# Power.net
KiCad netlist of a schematic drawn in Altium Designer
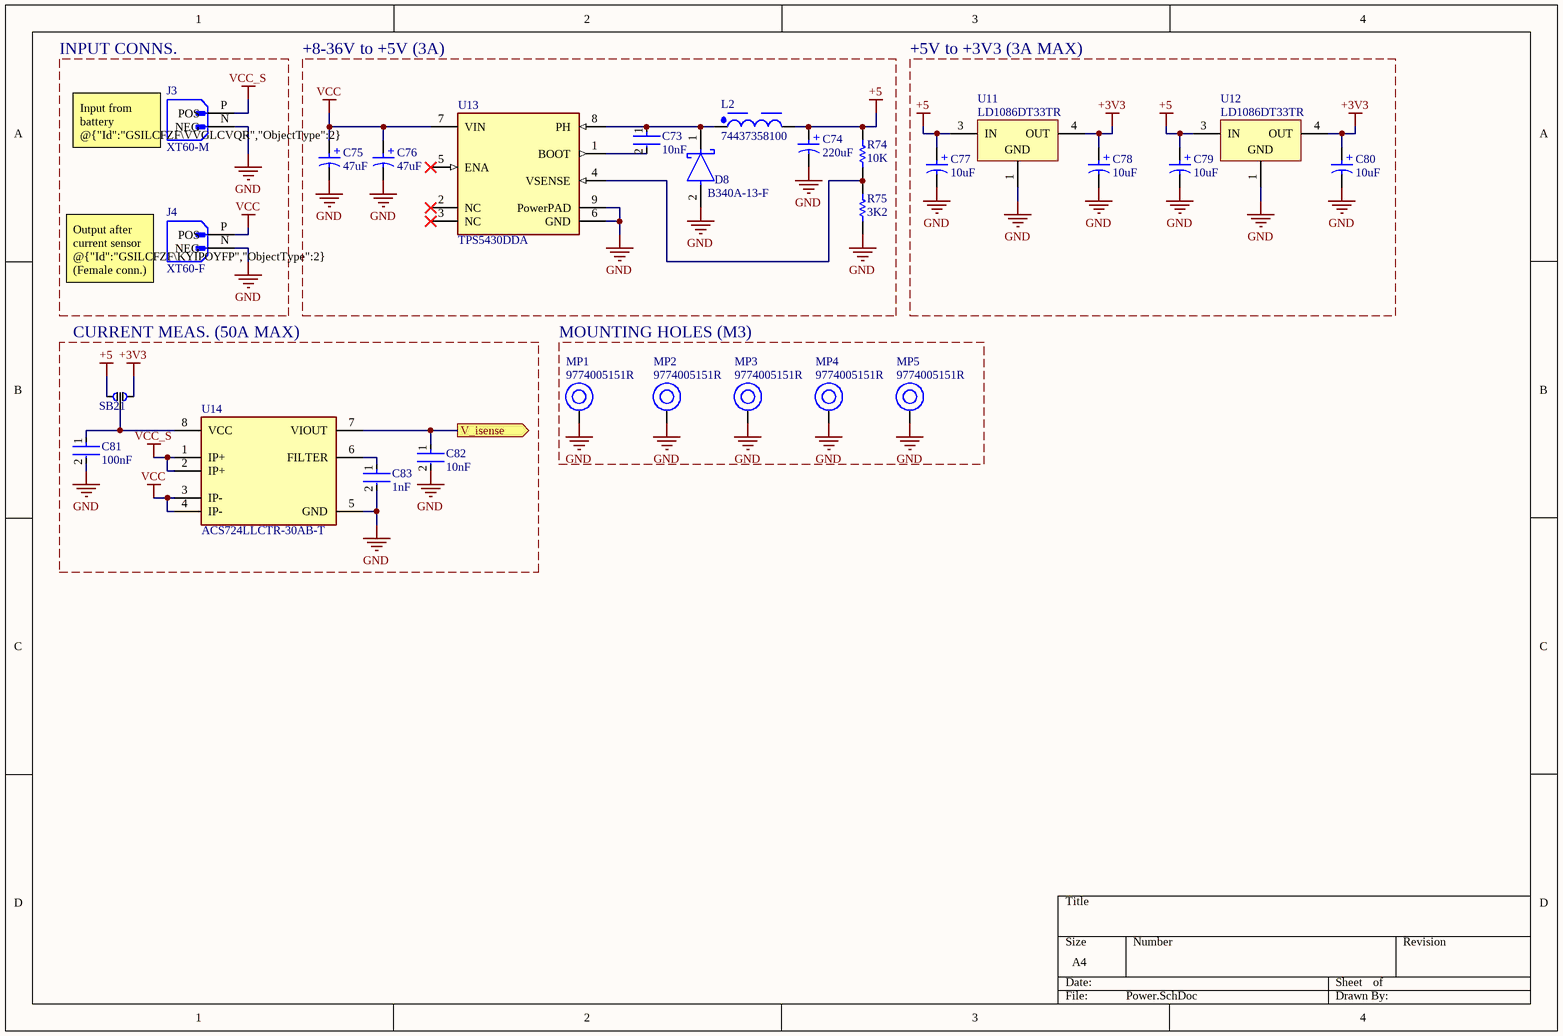
[diagram p0: Power.SchDoc]

(export (version "E")
  (design (tool "Eeschema 10.0.6"))
  (components
    (comp (ref "C73")
      (value "10nF")
      (footprint "FP-GRM188-0_1-e0_2_0_55-IPC_A")
      (description "Chip Multilayer Ceramic Capacitors for General Purpose, 0603, 10uF, X5R, 15%, 20%, 6.3V")
      (fields (field (name "VOLTAGE") "6.3V") (field (name "TOLERANCE") "20%"))
      (libsource (lib "Altium Content Vault") (part "02cd4be3c70576c341d710602a673aa"))
    )
    (comp (ref "C74")
      (value "220uF")
      (footprint "WCAP-ASLI_D8H10.5")
      (description "865080553014 Alum. Electrolytic Cap 220µF 35V 8mmV-Chip WCAP-ASLI; Lifetime 2000h +105°C")
      (fields (field (name "TOLERANCE") "20%"))
      (libsource (lib "Altium Content Vault") (part "Capacitor_Polarized"))
    )
    (comp (ref "C75")
      (value "47uF")
      (footprint "WCAP-PSLP_D6.3H7.7")
      (description "875105645005 Cap, 47Uf, 35V, Alu Elec Smd, Polymer Rohs Compliant: Yes")
      (libsource (lib "Altium Content Vault") (part "Capacitor_Polarized"))
    )
    (comp (ref "C76")
      (value "47uF")
      (footprint "WCAP-PSLP_D6.3H7.7")
      (description "875105645005 Cap, 47Uf, 35V, Alu Elec Smd, Polymer Rohs Compliant: Yes")
      (libsource (lib "Altium Content Vault") (part "Capacitor_Polarized"))
    )
    (comp (ref "C77")
      (value "10uF")
      (footprint "WCAP-ASLL_D6.3H5.5")
      (description "865060643005 WCAP-ASLL Aluminum Electrolytic Capacitors")
      (fields (field (name "TOLERANCE") "20%"))
      (libsource (lib "Altium Content Vault") (part "Capacitor_Polarized"))
    )
    (comp (ref "C78")
      (value "10uF")
      (footprint "WCAP-ASLL_D6.3H5.5")
      (description "865060643005 WCAP-ASLL Aluminum Electrolytic Capacitors")
      (fields (field (name "TOLERANCE") "20%"))
      (libsource (lib "Altium Content Vault") (part "Capacitor_Polarized"))
    )
    (comp (ref "C79")
      (value "10uF")
      (footprint "WCAP-ASLL_D6.3H5.5")
      (description "865060643005 WCAP-ASLL Aluminum Electrolytic Capacitors")
      (fields (field (name "TOLERANCE") "20%"))
      (libsource (lib "Altium Content Vault") (part "Capacitor_Polarized"))
    )
    (comp (ref "C80")
      (value "10uF")
      (footprint "WCAP-ASLL_D6.3H5.5")
      (description "865060643005 WCAP-ASLL Aluminum Electrolytic Capacitors")
      (fields (field (name "TOLERANCE") "20%"))
      (libsource (lib "Altium Content Vault") (part "Capacitor_Polarized"))
    )
    (comp (ref "C81")
      (value "100nF")
      (footprint "FP-GRM188-0_1-e0_2_0_55-IPC_A")
      (description "Chip Multilayer Ceramic Capacitors for General Purpose, 0603, 10uF, X5R, 15%, 20%, 6.3V")
      (fields (field (name "VOLTAGE") "6.3V") (field (name "TOLERANCE") "20%"))
      (libsource (lib "Altium Content Vault") (part "02cd4be3c70576c341d710602a673aa"))
    )
    (comp (ref "C82")
      (value "10nF")
      (footprint "FP-GRM188-0_1-e0_2_0_55-IPC_A")
      (description "Chip Multilayer Ceramic Capacitors for General Purpose, 0603, 10uF, X5R, 15%, 20%, 6.3V")
      (fields (field (name "VOLTAGE") "6.3V") (field (name "TOLERANCE") "20%"))
      (libsource (lib "Altium Content Vault") (part "02cd4be3c70576c341d710602a673aa"))
    )
    (comp (ref "C83")
      (value "1nF")
      (footprint "FP-GRM188-0_1-e0_2_0_55-IPC_A")
      (description "Chip Multilayer Ceramic Capacitors for General Purpose, 0603, 10uF, X5R, 15%, 20%, 6.3V")
      (fields (field (name "VOLTAGE") "6.3V") (field (name "TOLERANCE") "20%"))
      (libsource (lib "Altium Content Vault") (part "02cd4be3c70576c341d710602a673aa"))
    )
    (comp (ref "D8")
      (value "B340A-13-F")
      (footprint "FP-SMA-MFG")
      (description "DIODE SCHOTTKY 40V 3A SMA")
      (fields (field (name "VOLTAGE") "40V"))
      (libsource (lib "Altium Content Vault") (part "1d6ec82d83fb6aee721767c19dac4b9"))
    )
    (comp (ref "J3")
      (value "XT60-M")
      (footprint "AMASS_XT60-M")
      (description "Plug; DC supply; XT60; male; PIN: 2; for cable; soldered; 30A; 500V")
      (fields (field (name "MF") "AMASS"))
      (libsource (lib "XT60-M") (part "XT60-M"))
    )
    (comp (ref "J4")
      (value "XT60-F")
      (footprint "AMASS_XT60-M")
      (description "Plug; DC supply; XT60; male; PIN: 2; for cable; soldered; 30A; 500V")
      (fields (field (name "MF") "AMASS") (field (name "MP") "XT60-M"))
      (libsource (lib "XT60-M") (part "XT60-M"))
    )
    (comp (ref "L2")
      (value "74437358100")
      (footprint "WE-LHMI_8040")
      (description "74437358100 Power Inductor, 10Uh, Shielded, 4.5A Rohs Compliant: Yes")
      (fields (field (name "TOLERANCE") "20%"))
      (libsource (lib "Altium Content Vault") (part "Inductor - 2"))
    )
    (comp (ref "MP1")
      (value "9774005151R")
      (footprint "9774005151")
      (description "9774005151R WA-SMSI SMT Steel Spacer, M2.5 Internal non Stop")
      (libsource (lib "Altium Content Vault") (part "Spacer"))
    )
    (comp (ref "MP2")
      (value "9774005151R")
      (footprint "9774005151")
      (description "9774005151R WA-SMSI SMT Steel Spacer, M2.5 Internal non Stop")
      (libsource (lib "Altium Content Vault") (part "Spacer"))
    )
    (comp (ref "MP3")
      (value "9774005151R")
      (footprint "9774005151")
      (description "9774005151R WA-SMSI SMT Steel Spacer, M2.5 Internal non Stop")
      (libsource (lib "Altium Content Vault") (part "Spacer"))
    )
    (comp (ref "MP4")
      (value "9774005151R")
      (footprint "9774005151")
      (description "9774005151R WA-SMSI SMT Steel Spacer, M2.5 Internal non Stop")
      (libsource (lib "Altium Content Vault") (part "Spacer"))
    )
    (comp (ref "MP5")
      (value "9774005151R")
      (footprint "9774005151")
      (description "9774005151R WA-SMSI SMT Steel Spacer, M2.5 Internal non Stop")
      (libsource (lib "Altium Content Vault") (part "Spacer"))
    )
    (comp (ref "R74")
      (value "10K")
      (footprint "RESC1608X90X30ML15T20")
      (fields (field (name "PART NUMBER") "ERT-J1VR103J") (field (name "MANUFACTURER") "Panasonic"))
      (libsource (lib "Altium Content Vault") (part "RES"))
    )
    (comp (ref "R75")
      (value "3K2")
      (footprint "RESC1608X90X30ML15T20")
      (fields (field (name "PART NUMBER") "ERT-J1VR103J") (field (name "MANUFACTURER") "Panasonic"))
      (libsource (lib "Altium Content Vault") (part "RES"))
    )
    (comp (ref "SB21")
      (value "Solderbridge3P")
      (footprint "SolderBridge3P")
      (libsource (lib "Solder_Bridge") (part "Solderbridge3P"))
    )
    (comp (ref "U11")
      (value "LD1086DT33TR")
      (footprint "TO-252_L")
      (description "1.5A, Low Drop Positive Voltage Regulator, 3.3V, 3-Pin DPAK, Tape and Reel")
      (libsource (lib "Altium Content Vault") (part "PM-REG-LD1085-SOT3"))
    )
    (comp (ref "U12")
      (value "LD1086DT33TR")
      (footprint "TO-252_L")
      (description "1.5A, Low Drop Positive Voltage Regulator, 3.3V, 3-Pin DPAK, Tape and Reel")
      (libsource (lib "Altium Content Vault") (part "PM-REG-LD1085-SOT3"))
    )
    (comp (ref "U13")
      (value "TPS5430DDA")
      (footprint "FP-DDA0008J-MFG")
      (description "IC REG BUCK ADJUSTABLE 3A 8SOPWR")
      (fields
        (field (name "MANUFACTURER") "Texas Instruments")
        (field (name "OCTOPART") "https://octopart.com/tps5430dda-texas+instruments-589977")
      )
      (libsource (lib "Altium Content Vault") (part "98da629940cea6febc5630bb55159f3"))
    )
    (comp (ref "U14")
      (value "ACS724LLCTR-30AB-T")
      (footprint "FP-LCN-8-IPC_A")
      (description "SENSOR CURRENT HALL 30A AC/DC")
      (libsource (lib "Altium Content Vault") (part "24c2fda9b8a0b4b902445efe0d7face"))
    )
  )
  (nets
    (net (code "1") (name "+3V3") (class "Default")
      (node (ref "C78") (pin "1") (pinfunction "P_1") (pintype "passive"))
      (node (ref "C80") (pin "1") (pinfunction "P_1") (pintype "passive"))
      (node (ref "SB21") (pin "2") (pinfunction "2_2") (pintype "passive"))
      (node (ref "U11") (pin "4") (pinfunction "OUT_4") (pintype "power_in"))
      (node (ref "U12") (pin "4") (pinfunction "OUT_4") (pintype "power_in"))
    )
    (net (code "2") (name "+5") (class "Default")
      (node (ref "C74") (pin "1") (pinfunction "P_1") (pintype "passive"))
      (node (ref "C77") (pin "1") (pinfunction "P_1") (pintype "passive"))
      (node (ref "C79") (pin "1") (pinfunction "P_1") (pintype "passive"))
      (node (ref "L2") (pin "2") (pinfunction "2_2") (pintype "passive"))
      (node (ref "R74") (pin "2") (pinfunction "2_2") (pintype "passive"))
      (node (ref "SB21") (pin "1") (pinfunction "1_1") (pintype "passive"))
      (node (ref "U11") (pin "3") (pinfunction "IN_3") (pintype "power_in"))
      (node (ref "U12") (pin "3") (pinfunction "IN_3") (pintype "power_in"))
    )
    (net (code "3") (name "/V_isense") (class "Default")
      (node (ref "C82") (pin "1") (pinfunction "1_1") (pintype "passive"))
      (node (ref "U14") (pin "7") (pinfunction "VIOUT_7") (pintype "passive"))
    )
    (net (code "4") (name "GND") (class "Default")
      (node (ref "C74") (pin "2") (pinfunction "N_2") (pintype "passive"))
      (node (ref "C75") (pin "2") (pinfunction "N_2") (pintype "passive"))
      (node (ref "C76") (pin "2") (pinfunction "N_2") (pintype "passive"))
      (node (ref "C77") (pin "2") (pinfunction "N_2") (pintype "passive"))
      (node (ref "C78") (pin "2") (pinfunction "N_2") (pintype "passive"))
      (node (ref "C79") (pin "2") (pinfunction "N_2") (pintype "passive"))
      (node (ref "C80") (pin "2") (pinfunction "N_2") (pintype "passive"))
      (node (ref "C81") (pin "2") (pinfunction "2_2") (pintype "passive"))
      (node (ref "C82") (pin "2") (pinfunction "2_2") (pintype "passive"))
      (node (ref "C83") (pin "2") (pinfunction "2_2") (pintype "passive"))
      (node (ref "D8") (pin "2") (pinfunction "A_2") (pintype "passive"))
      (node (ref "J3") (pin "N") (pinfunction "NEG_N") (pintype "passive"))
      (node (ref "J4") (pin "N") (pinfunction "NEG_N") (pintype "passive"))
      (node (ref "MP1") (pin "1") (pinfunction "1_1") (pintype "passive"))
      (node (ref "MP2") (pin "1") (pinfunction "1_1") (pintype "passive"))
      (node (ref "MP3") (pin "1") (pinfunction "1_1") (pintype "passive"))
      (node (ref "MP4") (pin "1") (pinfunction "1_1") (pintype "passive"))
      (node (ref "MP5") (pin "1") (pinfunction "1_1") (pintype "passive"))
      (node (ref "R75") (pin "1") (pinfunction "1_1") (pintype "passive"))
      (node (ref "U11") (pin "1") (pinfunction "GND_1") (pintype "power_in"))
      (node (ref "U12") (pin "1") (pinfunction "GND_1") (pintype "power_in"))
      (node (ref "U13") (pin "6") (pinfunction "GND_6") (pintype "power_in"))
      (node (ref "U13") (pin "9") (pinfunction "PowerPAD_9") (pintype "power_in"))
      (node (ref "U14") (pin "5") (pinfunction "GND_5") (pintype "power_in"))
    )
    (net (code "5") (name "Net-(D8-C)") (class "Default")
      (node (ref "C73") (pin "1") (pinfunction "1_1") (pintype "passive"))
      (node (ref "D8") (pin "1") (pinfunction "C_1") (pintype "passive"))
      (node (ref "L2") (pin "1") (pinfunction "1_1") (pintype "passive"))
      (node (ref "U13") (pin "8") (pinfunction "PH_8") (pintype "input"))
    )
    (net (code "6") (name "Net-(U13-BOOT)") (class "Default")
      (node (ref "C73") (pin "2") (pinfunction "2_2") (pintype "passive"))
      (node (ref "U13") (pin "1") (pinfunction "BOOT_1") (pintype "output"))
    )
    (net (code "7") (name "Net-(U13-VSENSE)") (class "Default")
      (node (ref "R74") (pin "1") (pinfunction "1_1") (pintype "passive"))
      (node (ref "R75") (pin "2") (pinfunction "2_2") (pintype "passive"))
      (node (ref "U13") (pin "4") (pinfunction "VSENSE_4") (pintype "input"))
    )
    (net (code "8") (name "Net-(U14-FILTER)") (class "Default")
      (node (ref "C83") (pin "1") (pinfunction "1_1") (pintype "passive"))
      (node (ref "U14") (pin "6") (pinfunction "FILTER_6") (pintype "passive"))
    )
    (net (code "9") (name "Net-(U14-VCC)") (class "Default")
      (node (ref "C81") (pin "1") (pinfunction "1_1") (pintype "passive"))
      (node (ref "SB21") (pin "3") (pinfunction "3_3") (pintype "power_in"))
      (node (ref "U14") (pin "8") (pinfunction "VCC_8") (pintype "power_in"))
    )
    (net (code "10") (name "VCC") (class "Default")
      (node (ref "C75") (pin "1") (pinfunction "P_1") (pintype "passive"))
      (node (ref "C76") (pin "1") (pinfunction "P_1") (pintype "passive"))
      (node (ref "J4") (pin "P") (pinfunction "POS_P") (pintype "passive"))
      (node (ref "U13") (pin "7") (pinfunction "VIN_7") (pintype "power_in"))
      (node (ref "U14") (pin "3") (pinfunction "IP-_3") (pintype "passive"))
      (node (ref "U14") (pin "4") (pinfunction "IP-_4") (pintype "passive"))
    )
    (net (code "11") (name "VCC_S") (class "Default")
      (node (ref "J3") (pin "P") (pinfunction "POS_P") (pintype "passive"))
      (node (ref "U14") (pin "1") (pinfunction "IP+_1") (pintype "passive"))
      (node (ref "U14") (pin "2") (pinfunction "IP+_2") (pintype "passive"))
    )
    (net (code "12") (name "unconnected-(U13-ENA-Pad5)") (class "Default")
      (node (ref "U13") (pin "5") (pinfunction "ENA_5") (pintype "input+no_connect"))
    )
    (net (code "13") (name "unconnected-(U13-NC-Pad2)") (class "Default")
      (node (ref "U13") (pin "2") (pinfunction "NC_2") (pintype "passive+no_connect"))
    )
    (net (code "14") (name "unconnected-(U13-NC-Pad3)") (class "Default")
      (node (ref "U13") (pin "3") (pinfunction "NC_3") (pintype "passive+no_connect"))
    )
  )
)
